# half-kw-batpack.net
KiCad netlist of a schematic drawn in EAGLE
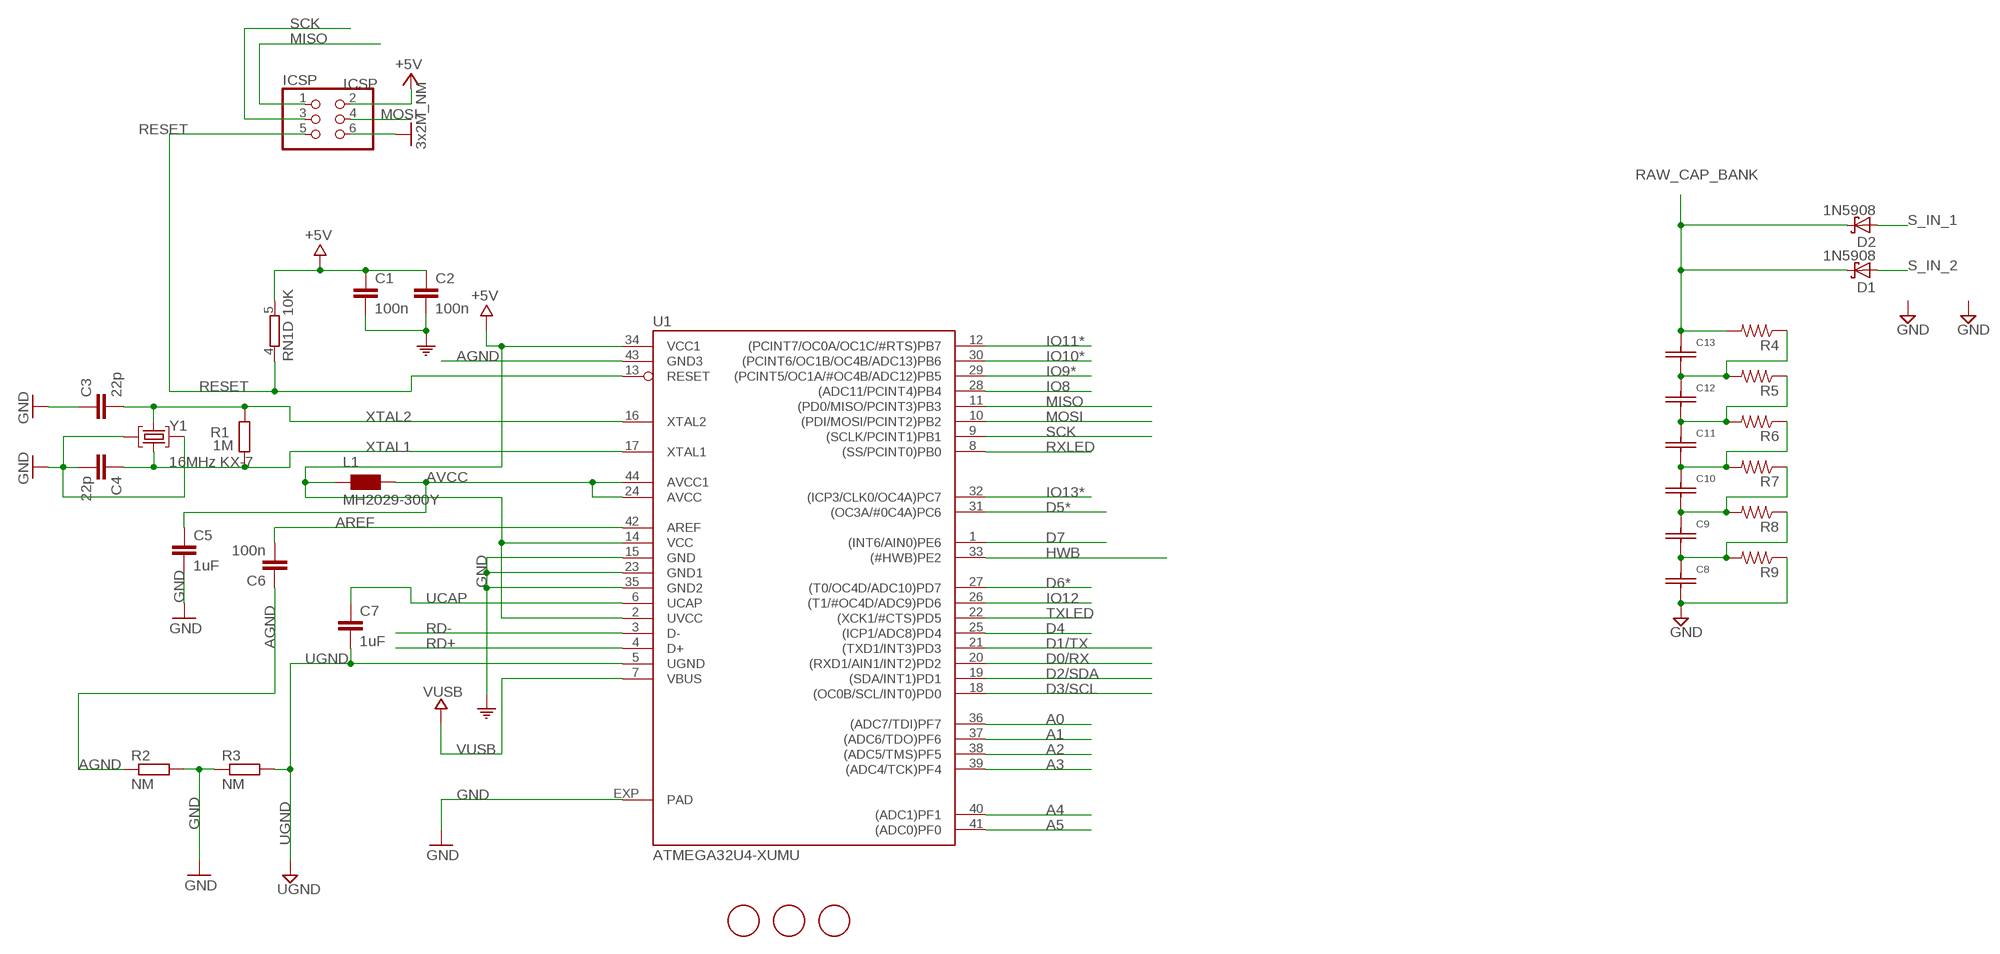
[diagram p0: schematic, sheet 1]
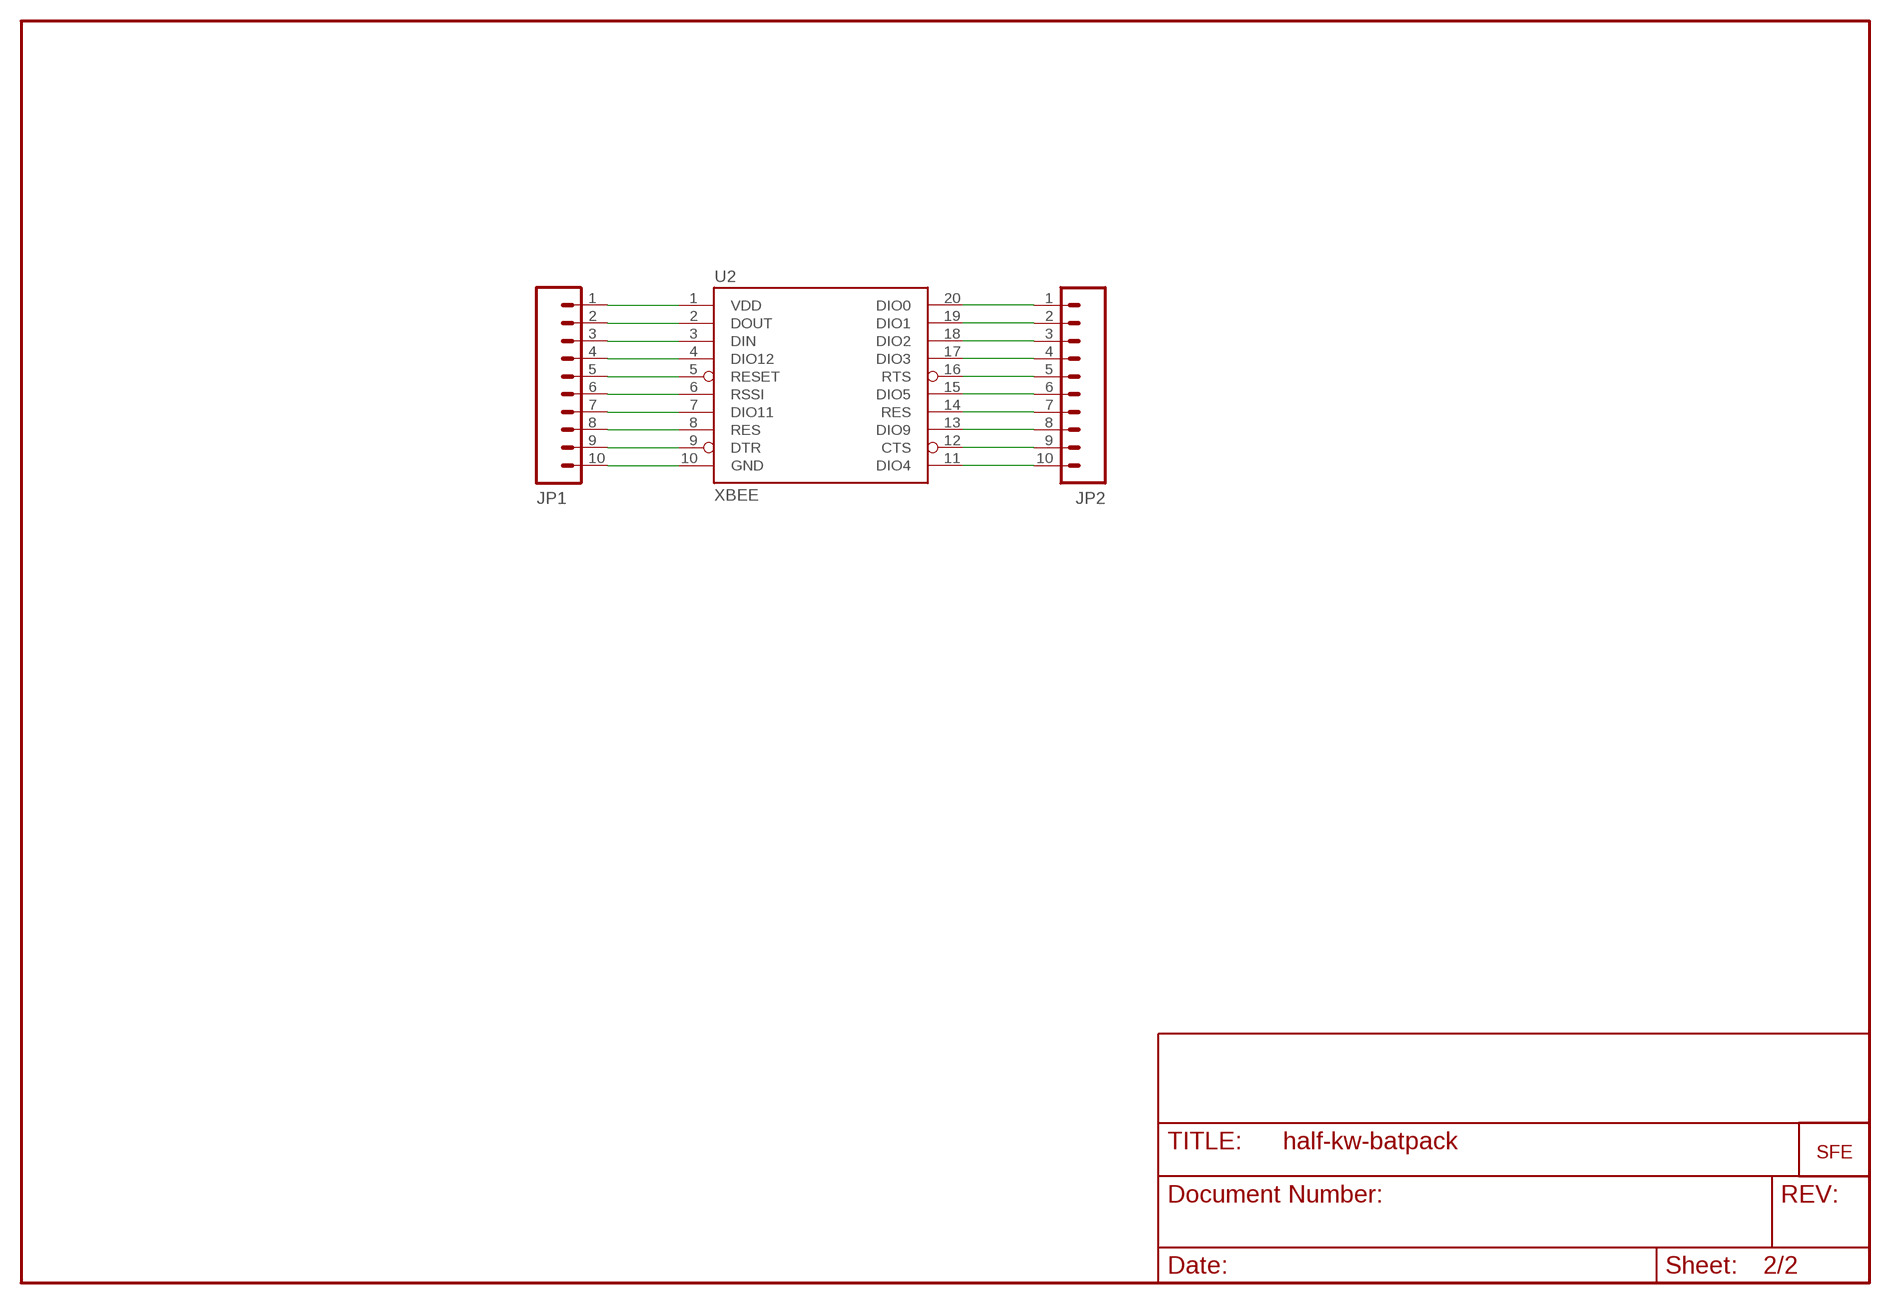
[diagram p1: schematic, sheet 2]

(export (version "E")
  (design (tool "Eeschema 10.0.6"))
  (components
    (comp (ref "C1")
      (value "100n")
      (footprint "eagle-import:C0603-ROUND")
      (libsource (lib "eagle-import") (part "C-EUC0603"))
    )
    (comp (ref "C2")
      (value "100n")
      (footprint "eagle-import:C0603-ROUND")
      (libsource (lib "eagle-import") (part "C-EUC0603"))
    )
    (comp (ref "C3")
      (value "22p")
      (footprint "eagle-import:C0603-ROUND")
      (libsource (lib "eagle-import") (part "C-EUC0603"))
    )
    (comp (ref "C4")
      (value "22p")
      (footprint "eagle-import:C0603-ROUND")
      (libsource (lib "eagle-import") (part "C-EUC0603"))
    )
    (comp (ref "C5")
      (value "1uF")
      (footprint "eagle-import:C0603-ROUND")
      (libsource (lib "eagle-import") (part "C-EUC0603"))
    )
    (comp (ref "C6")
      (value "100n")
      (footprint "eagle-import:C0603-ROUND")
      (libsource (lib "eagle-import") (part "C-EUC0603"))
    )
    (comp (ref "C7")
      (value "1uF")
      (footprint "eagle-import:C0603-ROUND")
      (libsource (lib "eagle-import") (part "C-EUC0603"))
    )
    (comp (ref "C8")
      (value "BCAP0100")
      (footprint "eagle-import:MAXWELLBCAP100")
      (fields (field (name "MFG") "maxwell"))
      (libsource (lib "eagle-import") (part "BCAP0100"))
    )
    (comp (ref "C9")
      (value "BCAP0100")
      (footprint "eagle-import:MAXWELLBCAP100")
      (fields (field (name "MFG") "maxwell"))
      (libsource (lib "eagle-import") (part "BCAP0100"))
    )
    (comp (ref "C10")
      (value "BCAP0100")
      (footprint "eagle-import:MAXWELLBCAP100")
      (fields (field (name "MFG") "maxwell"))
      (libsource (lib "eagle-import") (part "BCAP0100"))
    )
    (comp (ref "C11")
      (value "BCAP0100")
      (footprint "eagle-import:MAXWELLBCAP100")
      (fields (field (name "MFG") "maxwell"))
      (libsource (lib "eagle-import") (part "BCAP0100"))
    )
    (comp (ref "C12")
      (value "BCAP0100")
      (footprint "eagle-import:MAXWELLBCAP100")
      (fields (field (name "MFG") "maxwell"))
      (libsource (lib "eagle-import") (part "BCAP0100"))
    )
    (comp (ref "C13")
      (value "BCAP0100")
      (footprint "eagle-import:MAXWELLBCAP100")
      (fields (field (name "MFG") "maxwell"))
      (libsource (lib "eagle-import") (part "BCAP0100"))
    )
    (comp (ref "D1")
      (value "1N5908")
      (footprint "eagle-import:C4111-15")
      (libsource (lib "eagle-import") (part "1N5908"))
    )
    (comp (ref "D2")
      (value "1N5908")
      (footprint "eagle-import:C4111-15")
      (libsource (lib "eagle-import") (part "1N5908"))
    )
    (comp (ref "FID1")
      (value "FIDUCIALMOUNT")
      (footprint "eagle-import:FIDUCIA-MOUNT")
      (libsource (lib "eagle-import") (part "FIDUCIALMOUNT"))
    )
    (comp (ref "FID2")
      (value "FIDUCIALMOUNT")
      (footprint "eagle-import:FIDUCIA-MOUNT")
      (libsource (lib "eagle-import") (part "FIDUCIALMOUNT"))
    )
    (comp (ref "FID3")
      (value "FIDUCIALMOUNT")
      (footprint "eagle-import:FIDUCIA-MOUNT")
      (libsource (lib "eagle-import") (part "FIDUCIALMOUNT"))
    )
    (comp (ref "ICSP")
      (value "ICSP")
      (footprint "eagle-import:2X03")
      (libsource (lib "eagle-import") (part "PINHD-2X3"))
    )
    (comp (ref "L1")
      (value "MH2029-300Y")
      (footprint "eagle-import:0805")
      (libsource (lib "eagle-import") (part "WE-CBF_0805"))
    )
    (comp (ref "R1")
      (value "1M")
      (footprint "eagle-import:R0603-ROUND")
      (libsource (lib "eagle-import") (part "R-EU_R0603"))
    )
    (comp (ref "R2")
      (value "NM")
      (footprint "eagle-import:R0402")
      (libsource (lib "eagle-import") (part "R-EU_R0402"))
    )
    (comp (ref "R3")
      (value "NM")
      (footprint "eagle-import:R0402")
      (libsource (lib "eagle-import") (part "R-EU_R0402"))
    )
    (comp (ref "R4")
      (value "R-US_R1206")
      (footprint "eagle-import:R1206")
      (libsource (lib "eagle-import") (part "R-US_R1206"))
    )
    (comp (ref "R5")
      (value "R-US_R1206")
      (footprint "eagle-import:R1206")
      (libsource (lib "eagle-import") (part "R-US_R1206"))
    )
    (comp (ref "R6")
      (value "R-US_R1206")
      (footprint "eagle-import:R1206")
      (libsource (lib "eagle-import") (part "R-US_R1206"))
    )
    (comp (ref "R7")
      (value "R-US_R1206")
      (footprint "eagle-import:R1206")
      (libsource (lib "eagle-import") (part "R-US_R1206"))
    )
    (comp (ref "R8")
      (value "R-US_R1206")
      (footprint "eagle-import:R1206")
      (libsource (lib "eagle-import") (part "R-US_R1206"))
    )
    (comp (ref "R9")
      (value "R-US_R1206")
      (footprint "eagle-import:R1206")
      (libsource (lib "eagle-import") (part "R-US_R1206"))
    )
    (comp (ref "RN1")
      (value "10K")
      (footprint "eagle-import:CAY16")
      (libsource (lib "eagle-import") (part "4R-NCAY16"))
    )
    (comp (ref "U1")
      (value "ATMEGA32U4-XUMU")
      (footprint "eagle-import:QFN44ML7X7")
      (libsource (lib "eagle-import") (part "ATMEGA32U4-XUMU"))
    )
    (comp (ref "Y1")
      (value "16MHz KX-7")
      (footprint "eagle-import:CRYSTAL-3.2-2.5")
      (libsource (lib "eagle-import") (part "CRYSTAL-3.2-2.5"))
    )
    (comp (ref "JP1")
      (value "M100.1")
      (footprint "eagle-import:1X10")
      (libsource (lib "eagle-import") (part "M100.1"))
    )
    (comp (ref "JP2")
      (value "M100.1")
      (footprint "eagle-import:1X10")
      (libsource (lib "eagle-import") (part "M100.1"))
    )
    (comp (ref "U$2")
      (value "LOGO-SFENEW")
      (footprint "eagle-import:SFE-NEW-WEBLOGO")
      (libsource (lib "eagle-import") (part "LOGO-SFENEW"))
    )
    (comp (ref "U2")
      (value "XBEE")
      (footprint "eagle-import:XBEE-1")
      (libsource (lib "eagle-import") (part "XBEE-1B1"))
    )
  )
  (nets
    (net (code "1") (name "+5V") (class "Default")
      (node (ref "C1") (pin "1") (pinfunction "1_1") (pintype "passive"))
      (node (ref "C2") (pin "1") (pinfunction "1_1") (pintype "passive"))
      (node (ref "ICSP") (pin "2") (pinfunction "2_2") (pintype "passive"))
      (node (ref "L1") (pin "1") (pinfunction "1_1") (pintype "passive"))
      (node (ref "RN1") (pin "5") (pinfunction "2_5") (pintype "passive"))
      (node (ref "U1") (pin "14") (pinfunction "VCC_14") (pintype "power_in"))
      (node (ref "U1") (pin "2") (pinfunction "UVCC_2") (pintype "power_in"))
      (node (ref "U1") (pin "34") (pinfunction "VCC1_34") (pintype "power_in"))
    )
    (net (code "2") (name "A0") (class "Default")
      (node (ref "U1") (pin "36") (pinfunction "(ADC7/TDI)PF7_36") (pintype "bidirectional"))
    )
    (net (code "3") (name "A1") (class "Default")
      (node (ref "U1") (pin "37") (pinfunction "(ADC6/TDO)PF6_37") (pintype "bidirectional"))
    )
    (net (code "4") (name "A2") (class "Default")
      (node (ref "U1") (pin "38") (pinfunction "(ADC5/TMS)PF5_38") (pintype "bidirectional"))
    )
    (net (code "5") (name "A3") (class "Default")
      (node (ref "U1") (pin "39") (pinfunction "(ADC4/TCK)PF4_39") (pintype "bidirectional"))
    )
    (net (code "6") (name "A4") (class "Default")
      (node (ref "U1") (pin "40") (pinfunction "(ADC1)PF1_40") (pintype "bidirectional"))
    )
    (net (code "7") (name "A5") (class "Default")
      (node (ref "U1") (pin "41") (pinfunction "(ADC0)PF0_41") (pintype "bidirectional"))
    )
    (net (code "8") (name "AGND") (class "Default")
      (node (ref "C6") (pin "1") (pinfunction "1_1") (pintype "passive"))
      (node (ref "R2") (pin "1") (pinfunction "1_1") (pintype "passive"))
      (node (ref "U1") (pin "43") (pinfunction "GND3_43") (pintype "power_in"))
    )
    (net (code "9") (name "AREF") (class "Default")
      (node (ref "C6") (pin "2") (pinfunction "2_2") (pintype "passive"))
      (node (ref "U1") (pin "42") (pinfunction "AREF_42") (pintype "power_in"))
    )
    (net (code "10") (name "AVCC") (class "Default")
      (node (ref "C5") (pin "1") (pinfunction "1_1") (pintype "passive"))
      (node (ref "L1") (pin "2") (pinfunction "2_2") (pintype "passive"))
      (node (ref "U1") (pin "24") (pinfunction "AVCC_24") (pintype "power_in"))
      (node (ref "U1") (pin "44") (pinfunction "AVCC1_44") (pintype "power_in"))
    )
    (net (code "11") (name "D0{slash}RX") (class "Default")
      (node (ref "U1") (pin "20") (pinfunction "(RXD1/AIN1/INT2)PD2_20") (pintype "bidirectional"))
    )
    (net (code "12") (name "D1{slash}TX") (class "Default")
      (node (ref "U1") (pin "21") (pinfunction "(TXD1/INT3)PD3_21") (pintype "bidirectional"))
    )
    (net (code "13") (name "D2{slash}SDA") (class "Default")
      (node (ref "U1") (pin "19") (pinfunction "(SDA/INT1)PD1_19") (pintype "bidirectional"))
    )
    (net (code "14") (name "D3{slash}SCL") (class "Default")
      (node (ref "U1") (pin "18") (pinfunction "(OC0B/SCL/INT0)PD0_18") (pintype "bidirectional"))
    )
    (net (code "15") (name "D4") (class "Default")
      (node (ref "U1") (pin "25") (pinfunction "(ICP1/ADC8)PD4_25") (pintype "bidirectional"))
    )
    (net (code "16") (name "D5*") (class "Default")
      (node (ref "U1") (pin "31") (pinfunction "(OC3A/#0C4A)PC6_31") (pintype "bidirectional"))
    )
    (net (code "17") (name "D6*") (class "Default")
      (node (ref "U1") (pin "27") (pinfunction "(T0/OC4D/ADC10)PD7_27") (pintype "bidirectional"))
    )
    (net (code "18") (name "D7") (class "Default")
      (node (ref "U1") (pin "1") (pinfunction "(INT6/AIN0)PE6_1") (pintype "bidirectional"))
    )
    (net (code "19") (name "GND") (class "Default")
      (node (ref "C1") (pin "2") (pinfunction "2_2") (pintype "passive"))
      (node (ref "C2") (pin "2") (pinfunction "2_2") (pintype "passive"))
      (node (ref "C3") (pin "1") (pinfunction "1_1") (pintype "passive"))
      (node (ref "C4") (pin "2") (pinfunction "2_2") (pintype "passive"))
      (node (ref "C5") (pin "2") (pinfunction "2_2") (pintype "passive"))
      (node (ref "C8") (pin "P$2") (pinfunction "P$2_P$2") (pintype "bidirectional"))
      (node (ref "ICSP") (pin "6") (pinfunction "6_6") (pintype "passive"))
      (node (ref "R2") (pin "2") (pinfunction "2_2") (pintype "passive"))
      (node (ref "R3") (pin "1") (pinfunction "1_1") (pintype "passive"))
      (node (ref "R9") (pin "1") (pinfunction "1_1") (pintype "passive"))
      (node (ref "U1") (pin "15") (pinfunction "GND_15") (pintype "power_in"))
      (node (ref "U1") (pin "23") (pinfunction "GND1_23") (pintype "power_in"))
      (node (ref "U1") (pin "35") (pinfunction "GND2_35") (pintype "power_in"))
      (node (ref "U1") (pin "EXP") (pinfunction "PAD_EXP") (pintype "power_in"))
      (node (ref "Y1") (pin "2") (pinfunction "GND_2") (pintype "passive"))
      (node (ref "Y1") (pin "4") (pinfunction "GND_4") (pintype "passive"))
    )
    (net (code "20") (name "HWB") (class "Default")
      (node (ref "U1") (pin "33") (pinfunction "(#HWB)PE2_33") (pintype "bidirectional"))
    )
    (net (code "21") (name "IO8") (class "Default")
      (node (ref "U1") (pin "28") (pinfunction "(ADC11/PCINT4)PB4_28") (pintype "bidirectional"))
    )
    (net (code "22") (name "IO9*") (class "Default")
      (node (ref "U1") (pin "29") (pinfunction "(PCINT5/OC1A/#OC4B/ADC12)PB5_29") (pintype "bidirectional"))
    )
    (net (code "23") (name "IO10*") (class "Default")
      (node (ref "U1") (pin "30") (pinfunction "(PCINT6/OC1B/OC4B/ADC13)PB6_30") (pintype "bidirectional"))
    )
    (net (code "24") (name "IO11*") (class "Default")
      (node (ref "U1") (pin "12") (pinfunction "(PCINT7/OC0A/OC1C/#RTS)PB7_12") (pintype "bidirectional"))
    )
    (net (code "25") (name "IO12") (class "Default")
      (node (ref "U1") (pin "26") (pinfunction "(T1/#OC4D/ADC9)PD6_26") (pintype "bidirectional"))
    )
    (net (code "26") (name "IO13*") (class "Default")
      (node (ref "U1") (pin "32") (pinfunction "(ICP3/CLK0/OC4A)PC7_32") (pintype "bidirectional"))
    )
    (net (code "27") (name "MISO") (class "Default")
      (node (ref "ICSP") (pin "1") (pinfunction "1_1") (pintype "passive"))
      (node (ref "U1") (pin "11") (pinfunction "(PD0/MISO/PCINT3)PB3_11") (pintype "bidirectional"))
    )
    (net (code "28") (name "MOSI") (class "Default")
      (node (ref "ICSP") (pin "4") (pinfunction "4_4") (pintype "passive"))
      (node (ref "U1") (pin "10") (pinfunction "(PDI/MOSI/PCINT2)PB2_10") (pintype "bidirectional"))
    )
    (net (code "29") (name "Net-(C8-PadP$1)") (class "Default")
      (node (ref "C8") (pin "P$1") (pinfunction "P$1_P$1") (pintype "bidirectional"))
      (node (ref "C9") (pin "P$2") (pinfunction "P$2_P$2") (pintype "bidirectional"))
      (node (ref "R8") (pin "1") (pinfunction "1_1") (pintype "passive"))
      (node (ref "R9") (pin "2") (pinfunction "2_2") (pintype "passive"))
    )
    (net (code "30") (name "Net-(C10-PadP$1)") (class "Default")
      (node (ref "C10") (pin "P$1") (pinfunction "P$1_P$1") (pintype "bidirectional"))
      (node (ref "C11") (pin "P$2") (pinfunction "P$2_P$2") (pintype "bidirectional"))
      (node (ref "R6") (pin "1") (pinfunction "1_1") (pintype "passive"))
      (node (ref "R7") (pin "2") (pinfunction "2_2") (pintype "passive"))
    )
    (net (code "31") (name "Net-(C10-PadP$2)") (class "Default")
      (node (ref "C10") (pin "P$2") (pinfunction "P$2_P$2") (pintype "bidirectional"))
      (node (ref "C9") (pin "P$1") (pinfunction "P$1_P$1") (pintype "bidirectional"))
      (node (ref "R7") (pin "1") (pinfunction "1_1") (pintype "passive"))
      (node (ref "R8") (pin "2") (pinfunction "2_2") (pintype "passive"))
    )
    (net (code "32") (name "Net-(C11-PadP$1)") (class "Default")
      (node (ref "C11") (pin "P$1") (pinfunction "P$1_P$1") (pintype "bidirectional"))
      (node (ref "C12") (pin "P$2") (pinfunction "P$2_P$2") (pintype "bidirectional"))
      (node (ref "R5") (pin "1") (pinfunction "1_1") (pintype "passive"))
      (node (ref "R6") (pin "2") (pinfunction "2_2") (pintype "passive"))
    )
    (net (code "33") (name "Net-(C12-PadP$1)") (class "Default")
      (node (ref "C12") (pin "P$1") (pinfunction "P$1_P$1") (pintype "bidirectional"))
      (node (ref "C13") (pin "P$2") (pinfunction "P$2_P$2") (pintype "bidirectional"))
      (node (ref "R4") (pin "1") (pinfunction "1_1") (pintype "passive"))
      (node (ref "R5") (pin "2") (pinfunction "2_2") (pintype "passive"))
    )
    (net (code "34") (name "Net-(JP1-Pad8)") (class "Default")
      (node (ref "JP1") (pin "8") (pinfunction "8_8") (pintype "passive"))
      (node (ref "U2") (pin "8") (pinfunction "RES_8") (pintype "bidirectional"))
    )
    (net (code "35") (name "Net-(JP2-Pad7)") (class "Default")
      (node (ref "JP2") (pin "7") (pinfunction "7_7") (pintype "passive"))
      (node (ref "U2") (pin "14") (pinfunction "RES_14") (pintype "bidirectional"))
    )
    (net (code "36") (name "Net-(U2-CTS)") (class "Default")
      (node (ref "JP2") (pin "9") (pinfunction "9_9") (pintype "passive"))
      (node (ref "U2") (pin "12") (pinfunction "CTS_12") (pintype "output"))
    )
    (net (code "37") (name "Net-(U2-DIN)") (class "Default")
      (node (ref "JP1") (pin "3") (pinfunction "3_3") (pintype "passive"))
      (node (ref "U2") (pin "3") (pinfunction "DIN_3") (pintype "input"))
    )
    (net (code "38") (name "Net-(U2-DIO0)") (class "Default")
      (node (ref "JP2") (pin "1") (pinfunction "1_1") (pintype "passive"))
      (node (ref "U2") (pin "20") (pinfunction "DIO0_20") (pintype "bidirectional"))
    )
    (net (code "39") (name "Net-(U2-DIO1)") (class "Default")
      (node (ref "JP2") (pin "2") (pinfunction "2_2") (pintype "passive"))
      (node (ref "U2") (pin "19") (pinfunction "DIO1_19") (pintype "bidirectional"))
    )
    (net (code "40") (name "Net-(U2-DIO2)") (class "Default")
      (node (ref "JP2") (pin "3") (pinfunction "3_3") (pintype "passive"))
      (node (ref "U2") (pin "18") (pinfunction "DIO2_18") (pintype "bidirectional"))
    )
    (net (code "41") (name "Net-(U2-DIO3)") (class "Default")
      (node (ref "JP2") (pin "4") (pinfunction "4_4") (pintype "passive"))
      (node (ref "U2") (pin "17") (pinfunction "DIO3_17") (pintype "bidirectional"))
    )
    (net (code "42") (name "Net-(U2-DIO4)") (class "Default")
      (node (ref "JP2") (pin "10") (pinfunction "10_10") (pintype "passive"))
      (node (ref "U2") (pin "11") (pinfunction "DIO4_11") (pintype "bidirectional"))
    )
    (net (code "43") (name "Net-(U2-DIO5)") (class "Default")
      (node (ref "JP2") (pin "6") (pinfunction "6_6") (pintype "passive"))
      (node (ref "U2") (pin "15") (pinfunction "DIO5_15") (pintype "bidirectional"))
    )
    (net (code "44") (name "Net-(U2-DIO9)") (class "Default")
      (node (ref "JP2") (pin "8") (pinfunction "8_8") (pintype "passive"))
      (node (ref "U2") (pin "13") (pinfunction "DIO9_13") (pintype "bidirectional"))
    )
    (net (code "45") (name "Net-(U2-DIO11)") (class "Default")
      (node (ref "JP1") (pin "7") (pinfunction "7_7") (pintype "passive"))
      (node (ref "U2") (pin "7") (pinfunction "DIO11_7") (pintype "bidirectional"))
    )
    (net (code "46") (name "Net-(U2-DIO12)") (class "Default")
      (node (ref "JP1") (pin "4") (pinfunction "4_4") (pintype "passive"))
      (node (ref "U2") (pin "4") (pinfunction "DIO12_4") (pintype "bidirectional"))
    )
    (net (code "47") (name "Net-(U2-DOUT)") (class "Default")
      (node (ref "JP1") (pin "2") (pinfunction "2_2") (pintype "passive"))
      (node (ref "U2") (pin "2") (pinfunction "DOUT_2") (pintype "output"))
    )
    (net (code "48") (name "Net-(U2-DTR)") (class "Default")
      (node (ref "JP1") (pin "9") (pinfunction "9_9") (pintype "passive"))
      (node (ref "U2") (pin "9") (pinfunction "DTR_9") (pintype "bidirectional"))
    )
    (net (code "49") (name "Net-(U2-GND)") (class "Default")
      (node (ref "JP1") (pin "10") (pinfunction "10_10") (pintype "passive"))
      (node (ref "U2") (pin "10") (pinfunction "GND_10") (pintype "power_in"))
    )
    (net (code "50") (name "Net-(U2-RESET)") (class "Default")
      (node (ref "JP1") (pin "5") (pinfunction "5_5") (pintype "passive"))
      (node (ref "U2") (pin "5") (pinfunction "RESET_5") (pintype "input"))
    )
    (net (code "51") (name "Net-(U2-RSSI)") (class "Default")
      (node (ref "JP1") (pin "6") (pinfunction "6_6") (pintype "passive"))
      (node (ref "U2") (pin "6") (pinfunction "RSSI_6") (pintype "bidirectional"))
    )
    (net (code "52") (name "Net-(U2-RTS)") (class "Default")
      (node (ref "JP2") (pin "5") (pinfunction "5_5") (pintype "passive"))
      (node (ref "U2") (pin "16") (pinfunction "RTS_16") (pintype "input"))
    )
    (net (code "53") (name "Net-(U2-VDD)") (class "Default")
      (node (ref "JP1") (pin "1") (pinfunction "1_1") (pintype "passive"))
      (node (ref "U2") (pin "1") (pinfunction "VDD_1") (pintype "power_in"))
    )
    (net (code "54") (name "RAW_CAP_BANK") (class "Default")
      (node (ref "C13") (pin "P$1") (pinfunction "P$1_P$1") (pintype "bidirectional"))
      (node (ref "D1") (pin "C") (pinfunction "C_C") (pintype "passive"))
      (node (ref "D2") (pin "C") (pinfunction "C_C") (pintype "passive"))
      (node (ref "R4") (pin "2") (pinfunction "2_2") (pintype "passive"))
    )
    (net (code "55") (name "RD+") (class "Default")
      (node (ref "U1") (pin "4") (pinfunction "D+_4") (pintype "bidirectional"))
    )
    (net (code "56") (name "RD-") (class "Default")
      (node (ref "U1") (pin "3") (pinfunction "D-_3") (pintype "bidirectional"))
    )
    (net (code "57") (name "RESET") (class "Default")
      (node (ref "ICSP") (pin "5") (pinfunction "5_5") (pintype "passive"))
      (node (ref "RN1") (pin "4") (pinfunction "1_4") (pintype "passive"))
      (node (ref "U1") (pin "13") (pinfunction "RESET_13") (pintype "input"))
    )
    (net (code "58") (name "RXLED") (class "Default")
      (node (ref "U1") (pin "8") (pinfunction "(SS/PCINT0)PB0_8") (pintype "bidirectional"))
    )
    (net (code "59") (name "SCK") (class "Default")
      (node (ref "ICSP") (pin "3") (pinfunction "3_3") (pintype "passive"))
      (node (ref "U1") (pin "9") (pinfunction "(SCLK/PCINT1)PB1_9") (pintype "bidirectional"))
    )
    (net (code "60") (name "S_IN_1") (class "Default")
      (node (ref "D2") (pin "A") (pinfunction "A_A") (pintype "passive"))
    )
    (net (code "61") (name "S_IN_2") (class "Default")
      (node (ref "D1") (pin "A") (pinfunction "A_A") (pintype "passive"))
    )
    (net (code "62") (name "TXLED") (class "Default")
      (node (ref "U1") (pin "22") (pinfunction "(XCK1/#CTS)PD5_22") (pintype "bidirectional"))
    )
    (net (code "63") (name "UCAP") (class "Default")
      (node (ref "C7") (pin "1") (pinfunction "1_1") (pintype "passive"))
      (node (ref "U1") (pin "6") (pinfunction "UCAP_6") (pintype "passive"))
    )
    (net (code "64") (name "UGND") (class "Default")
      (node (ref "C7") (pin "2") (pinfunction "2_2") (pintype "passive"))
      (node (ref "R3") (pin "2") (pinfunction "2_2") (pintype "passive"))
      (node (ref "U1") (pin "5") (pinfunction "UGND_5") (pintype "power_in"))
    )
    (net (code "65") (name "VUSB") (class "Default")
      (node (ref "U1") (pin "7") (pinfunction "VBUS_7") (pintype "input"))
    )
    (net (code "66") (name "XTAL1") (class "Default")
      (node (ref "C4") (pin "1") (pinfunction "1_1") (pintype "passive"))
      (node (ref "R1") (pin "1") (pinfunction "1_1") (pintype "passive"))
      (node (ref "U1") (pin "17") (pinfunction "XTAL1_17") (pintype "bidirectional"))
      (node (ref "Y1") (pin "1") (pinfunction "C1_1") (pintype "passive"))
    )
    (net (code "67") (name "XTAL2") (class "Default")
      (node (ref "C3") (pin "2") (pinfunction "2_2") (pintype "passive"))
      (node (ref "R1") (pin "2") (pinfunction "2_2") (pintype "passive"))
      (node (ref "U1") (pin "16") (pinfunction "XTAL2_16") (pintype "bidirectional"))
      (node (ref "Y1") (pin "3") (pinfunction "C2_3") (pintype "passive"))
    )
  )
)
